# Schematic.net
KiCad netlist of a schematic drawn in Altium Designer
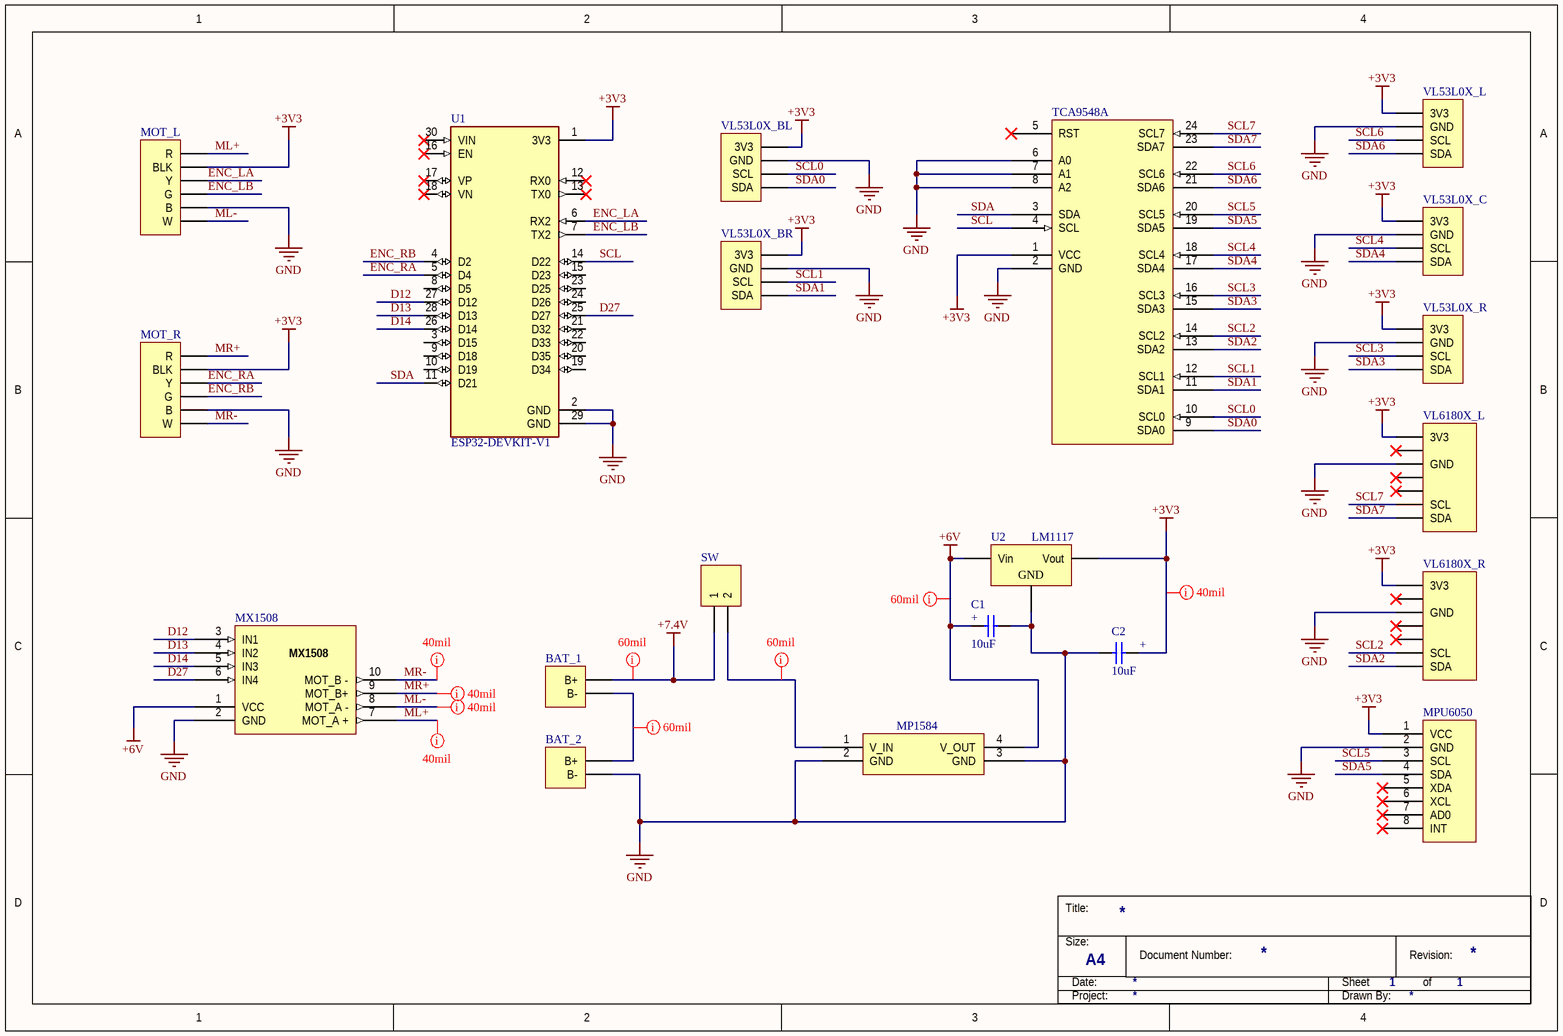
[diagram p0: Schematic.SchDoc]

(export (version "E")
  (design (tool "Eeschema 10.0.6"))
  (components
    (comp (ref "BAT_1")
      (value "Header 2")
      (footprint "MY_6410-02")
      (description "Header, 2-Pin")
      (fields (field (name "ASID PART NUMBER") "Header 2-AS"))
      (libsource (lib "Mylib+Rev+4") (part "Header 2"))
    )
    (comp (ref "BAT_2")
      (value "Header 2")
      (footprint "MY_6410-02")
      (description "Header, 2-Pin")
      (fields (field (name "ASID PART NUMBER") "Header 2-AS"))
      (libsource (lib "Mylib+Rev+4") (part "Header 2"))
    )
    (comp (ref "C1")
      (value "10uF")
      (footprint "MY_E2.5-5mm")
      (description "Polar capacitor")
      (fields (field (name "ASID PART NUMBER") "C-AS"))
      (libsource (lib "Mylib+Rev+4") (part "Cap Pol"))
    )
    (comp (ref "C2")
      (value "10uF")
      (footprint "MY_E2.5-5mm")
      (description "Polar capacitor")
      (fields (field (name "ASID PART NUMBER") "C-AS"))
      (libsource (lib "Mylib+Rev+4") (part "Cap Pol"))
    )
    (comp (ref "MOT_L")
      (value "Header 6")
      (footprint "MY_53253-0670")
      (description "Header, 6-Pin")
      (fields (field (name "ASID PART NUMBER") "Header 6-AS"))
      (libsource (lib "Mylib+Rev+4") (part "Header 6"))
    )
    (comp (ref "MOT_R")
      (value "Header 6")
      (footprint "MY_53253-0670")
      (description "Header, 6-Pin")
      (fields (field (name "ASID PART NUMBER") "Header 6-AS"))
      (libsource (lib "Mylib+Rev+4") (part "Header 6"))
    )
    (comp (ref "MP1584")
      (value "MP1584 Mini Adjustable Buck")
      (footprint "MP1584 Mini Adjustable Buck-Footprint-1")
      (libsource (lib "University of Moratuwa") (part "MP1584 Mini Adjustable Buck-Symbol-1"))
    )
    (comp (ref "MPU6050")
      (value "MPU6050 Accelerometer and Gyroscope Sensor")
      (footprint "MPU6050 Accelerometer and Gyroscope Sensor-Footprint-1")
      (libsource (lib "University of Moratuwa") (part "MPU6050 Accelerometer and Gyroscope Sensor-Symbol-1"))
    )
    (comp (ref "MX1508")
      (value "MX1508 Motor Driver")
      (footprint "MX1508 Motor Driver-Footprint-1")
      (description "MX1508 Dual H Bridge DC PWM Stepper Motor Driver module.")
      (libsource (lib "University of Moratuwa") (part "MX1508 Motor Driver-Symbol-1"))
    )
    (comp (ref "SW")
      (value "Header 2")
      (footprint "MY_6410-02")
      (description "Header, 2-Pin")
      (fields (field (name "ASID PART NUMBER") "Header 2-AS"))
      (libsource (lib "") (part "Header 2_1"))
    )
    (comp (ref "TCA9548A")
      (value "TCA9548A 1-to-8 I2C Multiplexer Module")
      (footprint "TCA9548A 1-to-8 I2C Multiplexer Module-Footprint-1")
      (libsource (lib "University of Moratuwa") (part "TCA9548A 1-to-8 I2C Multiplexer Module-Symbol-1"))
    )
    (comp (ref "U1")
      (value "ESP32-DEVKIT-V1")
      (footprint "MODULE_ESP32_DEVKIT_V1")
      (fields (field (name "MF") "{'manufacturer': u'Do it'}"))
      (libsource (lib "SnapEDA_Library") (part "ESP32-DEVKIT-V1"))
    )
    (comp (ref "U2")
      (value "LM1117")
      (footprint "MY_SOT223")
      (description "Low Drop Voltage Reg")
      (fields (field (name "ASID PART NUMBER") "LM1117-AS"))
      (libsource (lib "Mylib+Rev+4") (part "LM1117"))
    )
    (comp (ref "VL53L0X_BL")
      (value "Header 4")
      (footprint "MY_MA04-1W")
      (description "Header, 4-Pin")
      (fields (field (name "ASID PART NUMBER") "Header 4-AS"))
      (libsource (lib "Mylib+Rev+4") (part "Header 4"))
    )
    (comp (ref "VL53L0X_BR")
      (value "Header 4")
      (footprint "MY_MA04-1W")
      (description "Header, 4-Pin")
      (fields (field (name "ASID PART NUMBER") "Header 4-AS"))
      (libsource (lib "Mylib+Rev+4") (part "Header 4"))
    )
    (comp (ref "VL53L0X_C")
      (value "Header 4")
      (footprint "MY_MA04-1W")
      (description "Header, 4-Pin")
      (fields (field (name "ASID PART NUMBER") "Header 4-AS"))
      (libsource (lib "") (part "Header 4_1"))
    )
    (comp (ref "VL53L0X_L")
      (value "Header 4")
      (footprint "MY_MA04-1W")
      (description "Header, 4-Pin")
      (fields (field (name "ASID PART NUMBER") "Header 4-AS"))
      (libsource (lib "") (part "Header 4_1"))
    )
    (comp (ref "VL53L0X_R")
      (value "Header 4")
      (footprint "MY_MA04-1W")
      (description "Header, 4-Pin")
      (fields (field (name "ASID PART NUMBER") "Header 4-AS"))
      (libsource (lib "") (part "Header 4_1"))
    )
    (comp (ref "VL6180X_L")
      (value "Header 7")
      (footprint "MY_MA07-1W")
      (description "Header, 8-Pin, Dual row")
      (fields (field (name "ASID PART NUMBER") "Header 7-AS"))
      (libsource (lib "Mylib+Rev+4") (part "Header 7"))
    )
    (comp (ref "VL6180X_R")
      (value "Header 7")
      (footprint "MY_MA07-1W")
      (description "Header, 8-Pin, Dual row")
      (fields (field (name "ASID PART NUMBER") "Header 7-AS"))
      (libsource (lib "Mylib+Rev+4") (part "Header 7"))
    )
  )
  (nets
    (net (code "1") (name "+3V3") (class "Default")
      (node (ref "C2") (pin "+") (pinfunction "+_+") (pintype "passive"))
      (node (ref "MOT_L") (pin "2") (pinfunction "BLK_2") (pintype "passive"))
      (node (ref "MOT_R") (pin "2") (pinfunction "BLK_2") (pintype "passive"))
      (node (ref "MPU6050") (pin "1") (pinfunction "VCC_1") (pintype "power_in"))
      (node (ref "TCA9548A") (pin "1") (pinfunction "VCC_1") (pintype "power_in"))
      (node (ref "U1") (pin "1") (pinfunction "3V3_1") (pintype "power_in"))
      (node (ref "U2") (pin "2") (pinfunction "Vout_2") (pintype "passive"))
      (node (ref "VL53L0X_BL") (pin "1") (pinfunction "3V3_1") (pintype "passive"))
      (node (ref "VL53L0X_BR") (pin "1") (pinfunction "3V3_1") (pintype "passive"))
      (node (ref "VL53L0X_C") (pin "1") (pinfunction "3V3_1") (pintype "passive"))
      (node (ref "VL53L0X_L") (pin "1") (pinfunction "3V3_1") (pintype "passive"))
      (node (ref "VL53L0X_R") (pin "1") (pinfunction "3V3_1") (pintype "passive"))
      (node (ref "VL6180X_L") (pin "1") (pinfunction "3V3_1") (pintype "power_in"))
      (node (ref "VL6180X_R") (pin "1") (pinfunction "3V3_1") (pintype "power_in"))
    )
    (net (code "2") (name "+6V") (class "Default")
      (node (ref "C1") (pin "+") (pinfunction "+_+") (pintype "passive"))
      (node (ref "MP1584") (pin "4") (pinfunction "V_OUT_4") (pintype "power_in"))
      (node (ref "MX1508") (pin "1") (pinfunction "VCC_1") (pintype "power_in"))
      (node (ref "U2") (pin "3") (pinfunction "Vin_3") (pintype "passive"))
    )
    (net (code "3") (name "+7.4V") (class "Default")
      (node (ref "BAT_1") (pin "1") (pinfunction "B+_1") (pintype "passive"))
      (node (ref "SW") (pin "1") (pinfunction "1_1") (pintype "passive"))
    )
    (net (code "4") (name "/D12") (class "Default")
      (node (ref "MX1508") (pin "3") (pinfunction "IN1_3") (pintype "input"))
      (node (ref "U1") (pin "27") (pinfunction "D12_27") (pintype "bidirectional"))
    )
    (net (code "5") (name "/D13") (class "Default")
      (node (ref "MX1508") (pin "4") (pinfunction "IN2_4") (pintype "input"))
      (node (ref "U1") (pin "28") (pinfunction "D13_28") (pintype "bidirectional"))
    )
    (net (code "6") (name "/D14") (class "Default")
      (node (ref "MX1508") (pin "5") (pinfunction "IN3_5") (pintype "input"))
      (node (ref "U1") (pin "26") (pinfunction "D14_26") (pintype "bidirectional"))
    )
    (net (code "7") (name "/D27") (class "Default")
      (node (ref "MX1508") (pin "6") (pinfunction "IN4_6") (pintype "input"))
      (node (ref "U1") (pin "25") (pinfunction "D27_25") (pintype "bidirectional"))
    )
    (net (code "8") (name "/ENC_LA") (class "Default")
      (node (ref "MOT_L") (pin "3") (pinfunction "Y_3") (pintype "passive"))
      (node (ref "U1") (pin "6") (pinfunction "RX2_6") (pintype "input"))
    )
    (net (code "9") (name "/ENC_LB") (class "Default")
      (node (ref "MOT_L") (pin "4") (pinfunction "G_4") (pintype "passive"))
      (node (ref "U1") (pin "7") (pinfunction "TX2_7") (pintype "output"))
    )
    (net (code "10") (name "/ENC_RA") (class "Default")
      (node (ref "MOT_R") (pin "3") (pinfunction "Y_3") (pintype "passive"))
      (node (ref "U1") (pin "5") (pinfunction "D4_5") (pintype "bidirectional"))
    )
    (net (code "11") (name "/ENC_RB") (class "Default")
      (node (ref "MOT_R") (pin "4") (pinfunction "G_4") (pintype "passive"))
      (node (ref "U1") (pin "4") (pinfunction "D2_4") (pintype "bidirectional"))
    )
    (net (code "12") (name "/ML+") (class "Default")
      (node (ref "MOT_L") (pin "1") (pinfunction "R_1") (pintype "passive"))
      (node (ref "MX1508") (pin "7") (pinfunction "MOT_A_+_7") (pintype "output"))
    )
    (net (code "13") (name "/ML-") (class "Default")
      (node (ref "MOT_L") (pin "6") (pinfunction "W_6") (pintype "passive"))
      (node (ref "MX1508") (pin "8") (pinfunction "MOT_A_-_8") (pintype "output"))
    )
    (net (code "14") (name "/MR+") (class "Default")
      (node (ref "MOT_R") (pin "1") (pinfunction "R_1") (pintype "passive"))
      (node (ref "MX1508") (pin "9") (pinfunction "MOT_B+_9") (pintype "output"))
    )
    (net (code "15") (name "/MR-") (class "Default")
      (node (ref "MOT_R") (pin "6") (pinfunction "W_6") (pintype "passive"))
      (node (ref "MX1508") (pin "10") (pinfunction "MOT_B_-_10") (pintype "output"))
    )
    (net (code "16") (name "/SCL") (class "Default")
      (node (ref "TCA9548A") (pin "4") (pinfunction "SCL_4") (pintype "input"))
      (node (ref "U1") (pin "14") (pinfunction "D22_14") (pintype "bidirectional"))
    )
    (net (code "17") (name "/SCL0") (class "Default")
      (node (ref "TCA9548A") (pin "10") (pinfunction "SCL0_10") (pintype "input"))
      (node (ref "VL53L0X_BL") (pin "3") (pinfunction "SCL_3") (pintype "passive"))
    )
    (net (code "18") (name "/SCL1") (class "Default")
      (node (ref "TCA9548A") (pin "12") (pinfunction "SCL1_12") (pintype "input"))
      (node (ref "VL53L0X_BR") (pin "3") (pinfunction "SCL_3") (pintype "passive"))
    )
    (net (code "19") (name "/SCL2") (class "Default")
      (node (ref "TCA9548A") (pin "14") (pinfunction "SCL2_14") (pintype "input"))
      (node (ref "VL6180X_R") (pin "6") (pinfunction "SCL_6") (pintype "passive"))
    )
    (net (code "20") (name "/SCL3") (class "Default")
      (node (ref "TCA9548A") (pin "16") (pinfunction "SCL3_16") (pintype "input"))
      (node (ref "VL53L0X_R") (pin "3") (pinfunction "SCL_3") (pintype "passive"))
    )
    (net (code "21") (name "/SCL4") (class "Default")
      (node (ref "TCA9548A") (pin "18") (pinfunction "SCL4_18") (pintype "input"))
      (node (ref "VL53L0X_C") (pin "3") (pinfunction "SCL_3") (pintype "passive"))
    )
    (net (code "22") (name "/SCL5") (class "Default")
      (node (ref "MPU6050") (pin "3") (pinfunction "SCL_3") (pintype "passive"))
      (node (ref "TCA9548A") (pin "20") (pinfunction "SCL5_20") (pintype "input"))
    )
    (net (code "23") (name "/SCL6") (class "Default")
      (node (ref "TCA9548A") (pin "22") (pinfunction "SCL6_22") (pintype "input"))
      (node (ref "VL53L0X_L") (pin "3") (pinfunction "SCL_3") (pintype "passive"))
    )
    (net (code "24") (name "/SCL7") (class "Default")
      (node (ref "TCA9548A") (pin "24") (pinfunction "SCL7_24") (pintype "input"))
      (node (ref "VL6180X_L") (pin "6") (pinfunction "SCL_6") (pintype "passive"))
    )
    (net (code "25") (name "/SDA") (class "Default")
      (node (ref "TCA9548A") (pin "3") (pinfunction "SDA_3") (pintype "passive"))
      (node (ref "U1") (pin "11") (pinfunction "D21_11") (pintype "bidirectional"))
    )
    (net (code "26") (name "/SDA0") (class "Default")
      (node (ref "TCA9548A") (pin "9") (pinfunction "SDA0_9") (pintype "passive"))
      (node (ref "VL53L0X_BL") (pin "4") (pinfunction "SDA_4") (pintype "passive"))
    )
    (net (code "27") (name "/SDA1") (class "Default")
      (node (ref "TCA9548A") (pin "11") (pinfunction "SDA1_11") (pintype "passive"))
      (node (ref "VL53L0X_BR") (pin "4") (pinfunction "SDA_4") (pintype "passive"))
    )
    (net (code "28") (name "/SDA2") (class "Default")
      (node (ref "TCA9548A") (pin "13") (pinfunction "SDA2_13") (pintype "passive"))
      (node (ref "VL6180X_R") (pin "7") (pinfunction "SDA_7") (pintype "passive"))
    )
    (net (code "29") (name "/SDA3") (class "Default")
      (node (ref "TCA9548A") (pin "15") (pinfunction "SDA3_15") (pintype "passive"))
      (node (ref "VL53L0X_R") (pin "4") (pinfunction "SDA_4") (pintype "passive"))
    )
    (net (code "30") (name "/SDA4") (class "Default")
      (node (ref "TCA9548A") (pin "17") (pinfunction "SDA4_17") (pintype "passive"))
      (node (ref "VL53L0X_C") (pin "4") (pinfunction "SDA_4") (pintype "passive"))
    )
    (net (code "31") (name "/SDA5") (class "Default")
      (node (ref "MPU6050") (pin "4") (pinfunction "SDA_4") (pintype "passive"))
      (node (ref "TCA9548A") (pin "19") (pinfunction "SDA5_19") (pintype "passive"))
    )
    (net (code "32") (name "/SDA6") (class "Default")
      (node (ref "TCA9548A") (pin "21") (pinfunction "SDA6_21") (pintype "passive"))
      (node (ref "VL53L0X_L") (pin "4") (pinfunction "SDA_4") (pintype "passive"))
    )
    (net (code "33") (name "/SDA7") (class "Default")
      (node (ref "TCA9548A") (pin "23") (pinfunction "SDA7_23") (pintype "passive"))
      (node (ref "VL6180X_L") (pin "7") (pinfunction "SDA_7") (pintype "passive"))
    )
    (net (code "34") (name "GND") (class "Default")
      (node (ref "BAT_2") (pin "2") (pinfunction "B-_2") (pintype "passive"))
      (node (ref "C1") (pin "-") (pinfunction "-_-") (pintype "passive"))
      (node (ref "C2") (pin "-") (pinfunction "-_-") (pintype "passive"))
      (node (ref "MOT_L") (pin "5") (pinfunction "B_5") (pintype "passive"))
      (node (ref "MOT_R") (pin "5") (pinfunction "B_5") (pintype "passive"))
      (node (ref "MP1584") (pin "2") (pinfunction "GND_2") (pintype "power_in"))
      (node (ref "MP1584") (pin "3") (pinfunction "GND_3") (pintype "power_in"))
      (node (ref "MPU6050") (pin "2") (pinfunction "GND_2") (pintype "power_in"))
      (node (ref "MX1508") (pin "2") (pinfunction "GND_2") (pintype "power_in"))
      (node (ref "TCA9548A") (pin "2") (pinfunction "GND_2") (pintype "power_in"))
      (node (ref "TCA9548A") (pin "6") (pinfunction "A0_6") (pintype "passive"))
      (node (ref "TCA9548A") (pin "7") (pinfunction "A1_7") (pintype "passive"))
      (node (ref "TCA9548A") (pin "8") (pinfunction "A2_8") (pintype "passive"))
      (node (ref "U1") (pin "2") (pinfunction "GND_2") (pintype "power_in"))
      (node (ref "U1") (pin "29") (pinfunction "GND_29") (pintype "power_in"))
      (node (ref "U2") (pin "1") (pinfunction "GND_1") (pintype "passive"))
      (node (ref "VL53L0X_BL") (pin "2") (pinfunction "GND_2") (pintype "passive"))
      (node (ref "VL53L0X_BR") (pin "2") (pinfunction "GND_2") (pintype "passive"))
      (node (ref "VL53L0X_C") (pin "2") (pinfunction "GND_2") (pintype "passive"))
      (node (ref "VL53L0X_L") (pin "2") (pinfunction "GND_2") (pintype "passive"))
      (node (ref "VL53L0X_R") (pin "2") (pinfunction "GND_2") (pintype "passive"))
      (node (ref "VL6180X_L") (pin "3") (pinfunction "GND_3") (pintype "power_in"))
      (node (ref "VL6180X_R") (pin "3") (pinfunction "GND_3") (pintype "power_in"))
    )
    (net (code "35") (name "Net-(BAT_1-B-)") (class "Default")
      (node (ref "BAT_1") (pin "2") (pinfunction "B-_2") (pintype "passive"))
      (node (ref "BAT_2") (pin "1") (pinfunction "B+_1") (pintype "passive"))
    )
    (net (code "36") (name "Net-(MP1584-V_IN)") (class "Default")
      (node (ref "MP1584") (pin "1") (pinfunction "V_IN_1") (pintype "power_in"))
      (node (ref "SW") (pin "2") (pinfunction "2_2") (pintype "passive"))
    )
    (net (code "37") (name "unconnected-(MPU6050-AD0-Pad7)") (class "Default")
      (node (ref "MPU6050") (pin "7") (pinfunction "AD0_7") (pintype "passive+no_connect"))
    )
    (net (code "38") (name "unconnected-(MPU6050-INT-Pad8)") (class "Default")
      (node (ref "MPU6050") (pin "8") (pinfunction "INT_8") (pintype "passive+no_connect"))
    )
    (net (code "39") (name "unconnected-(MPU6050-XCL-Pad6)") (class "Default")
      (node (ref "MPU6050") (pin "6") (pinfunction "XCL_6") (pintype "passive+no_connect"))
    )
    (net (code "40") (name "unconnected-(MPU6050-XDA-Pad5)") (class "Default")
      (node (ref "MPU6050") (pin "5") (pinfunction "XDA_5") (pintype "passive+no_connect"))
    )
    (net (code "41") (name "unconnected-(TCA9548A-RST-Pad5)") (class "Default")
      (node (ref "TCA9548A") (pin "5") (pinfunction "RST_5") (pintype "passive+no_connect"))
    )
    (net (code "42") (name "unconnected-(U1-D5-Pad8)") (class "Default")
      (node (ref "U1") (pin "8") (pinfunction "D5_8") (pintype "bidirectional"))
    )
    (net (code "43") (name "unconnected-(U1-D15-Pad3)") (class "Default")
      (node (ref "U1") (pin "3") (pinfunction "D15_3") (pintype "bidirectional"))
    )
    (net (code "44") (name "unconnected-(U1-D18-Pad9)") (class "Default")
      (node (ref "U1") (pin "9") (pinfunction "D18_9") (pintype "bidirectional"))
    )
    (net (code "45") (name "unconnected-(U1-D19-Pad10)") (class "Default")
      (node (ref "U1") (pin "10") (pinfunction "D19_10") (pintype "bidirectional"))
    )
    (net (code "46") (name "unconnected-(U1-D23-Pad15)") (class "Default")
      (node (ref "U1") (pin "15") (pinfunction "D23_15") (pintype "bidirectional"))
    )
    (net (code "47") (name "unconnected-(U1-D25-Pad23)") (class "Default")
      (node (ref "U1") (pin "23") (pinfunction "D25_23") (pintype "bidirectional"))
    )
    (net (code "48") (name "unconnected-(U1-D26-Pad24)") (class "Default")
      (node (ref "U1") (pin "24") (pinfunction "D26_24") (pintype "bidirectional"))
    )
    (net (code "49") (name "unconnected-(U1-D32-Pad21)") (class "Default")
      (node (ref "U1") (pin "21") (pinfunction "D32_21") (pintype "bidirectional"))
    )
    (net (code "50") (name "unconnected-(U1-D33-Pad22)") (class "Default")
      (node (ref "U1") (pin "22") (pinfunction "D33_22") (pintype "bidirectional"))
    )
    (net (code "51") (name "unconnected-(U1-D34-Pad19)") (class "Default")
      (node (ref "U1") (pin "19") (pinfunction "D34_19") (pintype "bidirectional"))
    )
    (net (code "52") (name "unconnected-(U1-D35-Pad20)") (class "Default")
      (node (ref "U1") (pin "20") (pinfunction "D35_20") (pintype "bidirectional"))
    )
    (net (code "53") (name "unconnected-(U1-EN-Pad16)") (class "Default")
      (node (ref "U1") (pin "16") (pinfunction "EN_16") (pintype "input+no_connect"))
    )
    (net (code "54") (name "unconnected-(U1-RX0-Pad12)") (class "Default")
      (node (ref "U1") (pin "12") (pinfunction "RX0_12") (pintype "input+no_connect"))
    )
    (net (code "55") (name "unconnected-(U1-TX0-Pad13)") (class "Default")
      (node (ref "U1") (pin "13") (pinfunction "TX0_13") (pintype "output+no_connect"))
    )
    (net (code "56") (name "unconnected-(U1-VIN-Pad30)") (class "Default")
      (node (ref "U1") (pin "30") (pinfunction "VIN_30") (pintype "input+no_connect"))
    )
    (net (code "57") (name "unconnected-(U1-VN-Pad18)") (class "Default")
      (node (ref "U1") (pin "18") (pinfunction "VN_18") (pintype "bidirectional+no_connect"))
    )
    (net (code "58") (name "unconnected-(U1-VP-Pad17)") (class "Default")
      (node (ref "U1") (pin "17") (pinfunction "VP_17") (pintype "bidirectional+no_connect"))
    )
    (net (code "59") (name "unconnected-(VL6180X_L-Pad2)") (class "Default")
      (node (ref "VL6180X_L") (pin "2") (pinfunction "2_2") (pintype "passive+no_connect"))
    )
    (net (code "60") (name "unconnected-(VL6180X_L-Pad4)") (class "Default")
      (node (ref "VL6180X_L") (pin "4") (pinfunction "4_4") (pintype "passive+no_connect"))
    )
    (net (code "61") (name "unconnected-(VL6180X_L-Pad5)") (class "Default")
      (node (ref "VL6180X_L") (pin "5") (pinfunction "5_5") (pintype "passive+no_connect"))
    )
    (net (code "62") (name "unconnected-(VL6180X_R-Pad2)") (class "Default")
      (node (ref "VL6180X_R") (pin "2") (pinfunction "2_2") (pintype "passive+no_connect"))
    )
    (net (code "63") (name "unconnected-(VL6180X_R-Pad4)") (class "Default")
      (node (ref "VL6180X_R") (pin "4") (pinfunction "4_4") (pintype "passive+no_connect"))
    )
    (net (code "64") (name "unconnected-(VL6180X_R-Pad5)") (class "Default")
      (node (ref "VL6180X_R") (pin "5") (pinfunction "5_5") (pintype "passive+no_connect"))
    )
  )
)
